# MCU.net
KiCad netlist of a schematic drawn in Altium Designer
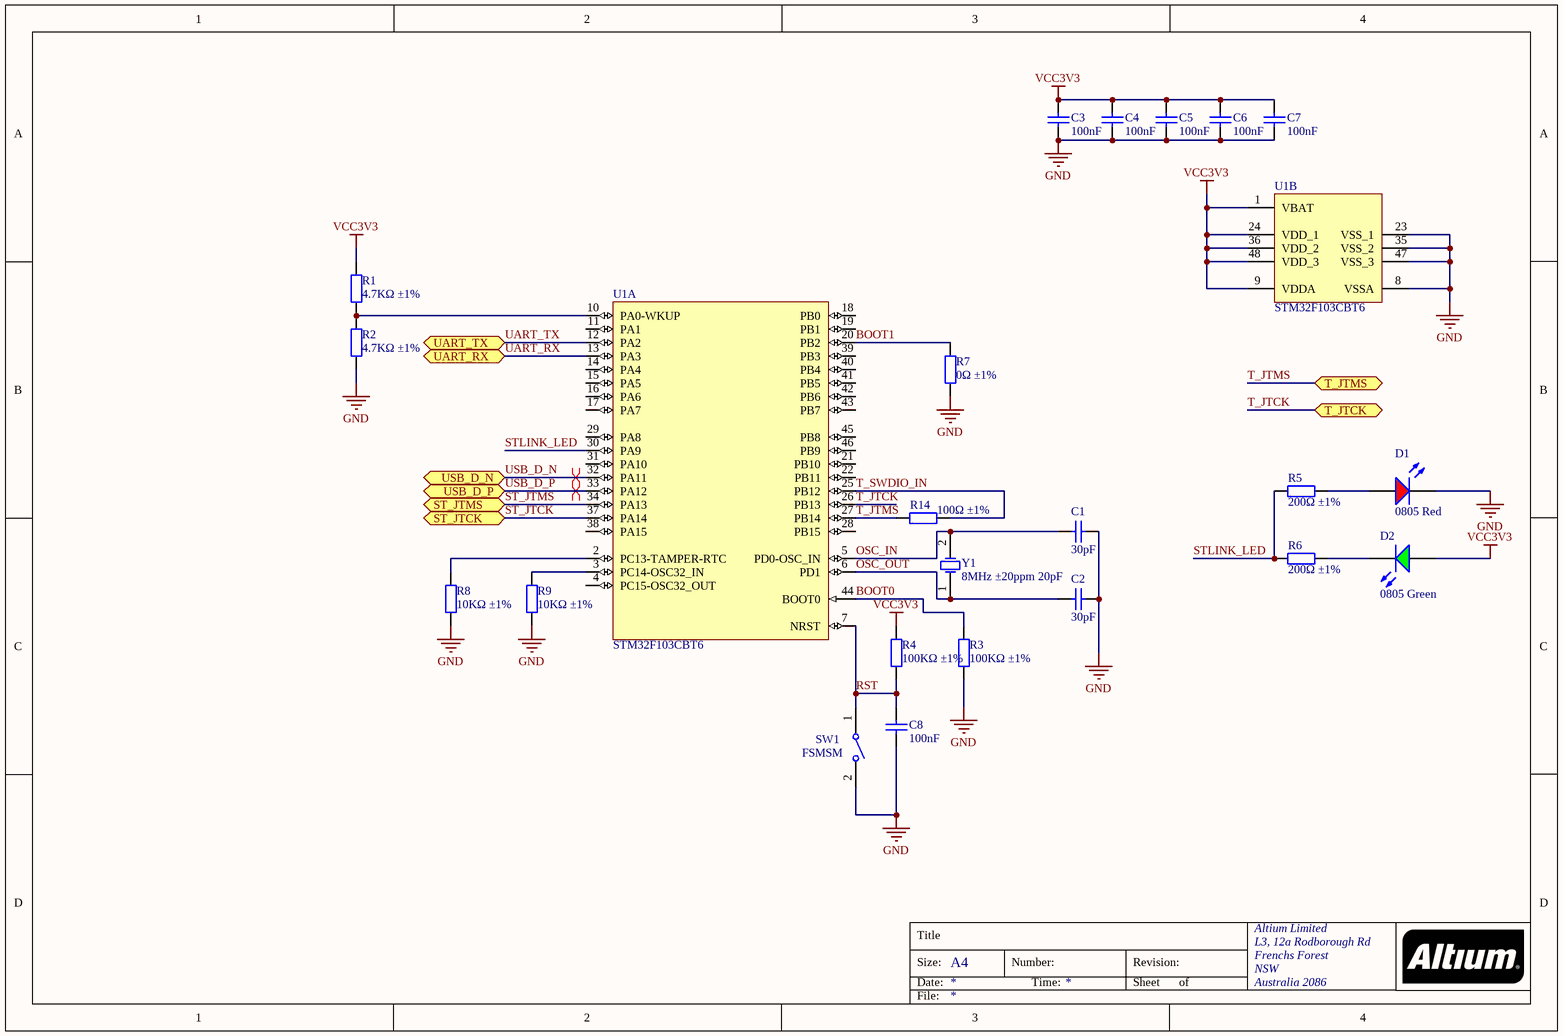
[diagram p0: MCU.SchDoc]

(export (version "E")
  (design (tool "Eeschema 10.0.6"))
  (components
    (comp (ref "C1")
      (value "30pF")
      (footprint "0402_C")
      (description "Chip capacitors")
      (fields
        (field (name "MANUFACTURER") "Guangdong Fenghua Advanced Tech")
        (field (name "PARTNUMBER") "0402CG300J500NT")
      )
      (libsource (lib "Miscellaneous Devices LC") (part "0402 30pF (300) 5% 50V"))
    )
    (comp (ref "C2")
      (value "30pF")
      (footprint "0402_C")
      (description "Chip capacitors")
      (fields
        (field (name "MANUFACTURER") "Guangdong Fenghua Advanced Tech")
        (field (name "PARTNUMBER") "0402CG300J500NT")
      )
      (libsource (lib "Miscellaneous Devices LC") (part "0402 30pF (300) 5% 50V"))
    )
    (comp (ref "C3")
      (value "100nF")
      (footprint "0402_C")
      (description "Chip capacitors")
      (fields
        (field (name "MANUFACTURER") "Samsung Electro-Mechanics")
        (field (name "PARTNUMBER") "CL05B104KO5NNNC")
      )
      (libsource (lib "Miscellaneous Devices LC") (part "0402 100nF (104) 10% 16V"))
    )
    (comp (ref "C4")
      (value "100nF")
      (footprint "0402_C")
      (description "Chip capacitors")
      (fields
        (field (name "MANUFACTURER") "Samsung Electro-Mechanics")
        (field (name "PARTNUMBER") "CL05B104KO5NNNC")
      )
      (libsource (lib "Miscellaneous Devices LC") (part "0402 100nF (104) 10% 16V"))
    )
    (comp (ref "C5")
      (value "100nF")
      (footprint "0402_C")
      (description "Chip capacitors")
      (fields
        (field (name "MANUFACTURER") "Samsung Electro-Mechanics")
        (field (name "PARTNUMBER") "CL05B104KO5NNNC")
      )
      (libsource (lib "Miscellaneous Devices LC") (part "0402 100nF (104) 10% 16V"))
    )
    (comp (ref "C6")
      (value "100nF")
      (footprint "0402_C")
      (description "Chip capacitors")
      (fields
        (field (name "MANUFACTURER") "Samsung Electro-Mechanics")
        (field (name "PARTNUMBER") "CL05B104KO5NNNC")
      )
      (libsource (lib "Miscellaneous Devices LC") (part "0402 100nF (104) 10% 16V"))
    )
    (comp (ref "C7")
      (value "100nF")
      (footprint "0402_C")
      (description "Chip capacitors")
      (fields
        (field (name "MANUFACTURER") "Samsung Electro-Mechanics")
        (field (name "PARTNUMBER") "CL05B104KO5NNNC")
      )
      (libsource (lib "Miscellaneous Devices LC") (part "0402 100nF (104) 10% 16V"))
    )
    (comp (ref "C8")
      (value "100nF")
      (footprint "0402_C")
      (description "Chip capacitors")
      (fields
        (field (name "MANUFACTURER") "Samsung Electro-Mechanics")
        (field (name "PARTNUMBER") "CL05B104KO5NNNC")
      )
      (libsource (lib "Miscellaneous Devices LC") (part "0402 100nF (104) 10% 16V"))
    )
    (comp (ref "D1")
      (value "0805 Red")
      (footprint "0805_LED_S1")
      (description "LED")
      (libsource (lib "Miscellaneous Devices LC") (part "0805 LED Red"))
    )
    (comp (ref "D2")
      (value "0805 Green")
      (footprint "0805_LED_S1")
      (description "LED")
      (libsource (lib "Miscellaneous Devices LC") (part "0805 LED Green"))
    )
    (comp (ref "R1")
      (value "4.7KΩ ±1%")
      (footprint "0805_R")
      (description "Chip resistor")
      (fields (field (name "MANUFACTURER") "Uniroyal Elec") (field (name "POWER") "1/8W"))
      (libsource (lib "Miscellaneous Devices LC") (part "0805 4.7K (4701) 1%"))
    )
    (comp (ref "R2")
      (value "4.7KΩ ±1%")
      (footprint "0805_R")
      (description "Chip resistor")
      (fields (field (name "MANUFACTURER") "Uniroyal Elec") (field (name "POWER") "1/8W"))
      (libsource (lib "Miscellaneous Devices LC") (part "0805 4.7K (4701) 1%"))
    )
    (comp (ref "R3")
      (value "100KΩ ±1%")
      (footprint "0402_R")
      (description "Chip resistor")
      (fields (field (name "MANUFACTURER") "Uniroyal Elec") (field (name "PARTNUMBER") "0402WGF1003TCE"))
      (libsource (lib "Miscellaneous Devices LC") (part "0402 100K (1003) 1%"))
    )
    (comp (ref "R4")
      (value "100KΩ ±1%")
      (footprint "0402_R")
      (description "Chip resistor")
      (fields (field (name "MANUFACTURER") "Uniroyal Elec") (field (name "PARTNUMBER") "0402WGF1003TCE"))
      (libsource (lib "Miscellaneous Devices LC") (part "0402 100K (1003) 1%"))
    )
    (comp (ref "R5")
      (value "200Ω ±1%")
      (footprint "0402_R")
      (description "Chip resistor")
      (fields (field (name "MANUFACTURER") "Uniroyal Elec") (field (name "PARTNUMBER") "0402WGF2000TCE"))
      (libsource (lib "Miscellaneous Devices LC") (part "0402 200R (2000) 1%"))
    )
    (comp (ref "R6")
      (value "200Ω ±1%")
      (footprint "0402_R")
      (description "Chip resistor")
      (fields (field (name "MANUFACTURER") "Uniroyal Elec") (field (name "PARTNUMBER") "0402WGF2000TCE"))
      (libsource (lib "Miscellaneous Devices LC") (part "0402 200R (2000) 1%"))
    )
    (comp (ref "R7")
      (value "0Ω ±1%")
      (footprint "0402_R")
      (description "Chip resistor")
      (fields (field (name "POWER") "1/16W") (field (name "MANUFACTURER") "Uniroyal Elec"))
      (libsource (lib "Miscellaneous Devices LC") (part "0402 0R (0R0) 1%"))
    )
    (comp (ref "R8")
      (value "10KΩ ±1%")
      (footprint "0402_R")
      (description "Chip resistor")
      (fields (field (name "MANUFACTURER") "Uniroyal Elec") (field (name "PARTNUMBER") "0402WGF1002TCE"))
      (libsource (lib "Miscellaneous Devices LC") (part "0402 10K (1002) 1%"))
    )
    (comp (ref "R9")
      (value "10KΩ ±1%")
      (footprint "0402_R")
      (description "Chip resistor")
      (fields (field (name "MANUFACTURER") "Uniroyal Elec") (field (name "PARTNUMBER") "0402WGF1002TCE"))
      (libsource (lib "Miscellaneous Devices LC") (part "0402 10K (1002) 1%"))
    )
    (comp (ref "R14")
      (value "100Ω ±1%")
      (footprint "0402_R")
      (description "Chip resistor")
      (fields (field (name "MANUFACTURER") "Uniroyal Elec") (field (name "PARTNUMBER") "0402WGF1000TCE"))
      (libsource (lib "Miscellaneous Devices LC") (part "0402 100R (1000) 1%"))
    )
    (comp (ref "SW1")
      (value "FSMSM")
      (footprint "TECO-FSMSM-2_V")
      (description "FSMSM Push Button Switch, 50 mA, -35 to 85 degC, 2-Pin SMD, RoHS, Bulk")
      (fields (field (name "MANUFACTURER") "TE Connectivity"))
      (libsource (lib "Altium Content Vault") (part "SW-SPST-2_C"))
    )
    (comp (ref "U1")
      (value "STM32F103CBT6")
      (footprint "LQFP-48_7x7x05P")
      (description "ARM")
      (libsource (lib "Miscellaneous Devices LC") (part "STM32F103CBT6"))
    )
    (comp (ref "Y1")
      (value "8MHz ±20ppm 20pF")
      (footprint "SMD-5032_2P")
      (description "贴片晶振")
      (libsource (lib "Miscellaneous Devices LC") (part "SMD-5032_2P 8MHz 20ppm 20pF"))
    )
  )
  (nets
    (net (code "1") (name "/BOOT0") (class "Default")
      (node (ref "R3") (pin "2") (pinfunction "2_2") (pintype "passive"))
      (node (ref "U1") (pin "44") (pinfunction "BOOT0_44") (pintype "input"))
    )
    (net (code "2") (name "/BOOT1") (class "Default")
      (node (ref "R7") (pin "2") (pinfunction "2_2") (pintype "passive"))
      (node (ref "U1") (pin "20") (pinfunction "PB2_20") (pintype "bidirectional"))
    )
    (net (code "3") (name "/OSC_IN") (class "Default")
      (node (ref "C1") (pin "1") (pinfunction "1_1") (pintype "passive"))
      (node (ref "U1") (pin "5") (pinfunction "PD0-OSC_IN_5") (pintype "bidirectional"))
      (node (ref "Y1") (pin "2") (pinfunction "OSC2_2") (pintype "passive"))
    )
    (net (code "4") (name "/OSC_OUT") (class "Default")
      (node (ref "C2") (pin "1") (pinfunction "1_1") (pintype "passive"))
      (node (ref "U1") (pin "6") (pinfunction "PD1_6") (pintype "bidirectional"))
      (node (ref "Y1") (pin "1") (pinfunction "OSC1_1") (pintype "passive"))
    )
    (net (code "5") (name "/RST") (class "Default")
      (node (ref "C8") (pin "2") (pinfunction "2_2") (pintype "passive"))
      (node (ref "R4") (pin "1") (pinfunction "1_1") (pintype "passive"))
      (node (ref "SW1") (pin "1") (pinfunction "1_1") (pintype "passive"))
      (node (ref "U1") (pin "7") (pinfunction "NRST_7") (pintype "bidirectional"))
    )
    (net (code "6") (name "/STLINK_LED") (class "Default")
      (node (ref "R5") (pin "1") (pinfunction "1_1") (pintype "passive"))
      (node (ref "R6") (pin "1") (pinfunction "1_1") (pintype "passive"))
      (node (ref "U1") (pin "30") (pinfunction "PA9_30") (pintype "bidirectional"))
    )
    (net (code "7") (name "/ST_JTCK") (class "Default")
      (node (ref "U1") (pin "37") (pinfunction "PA14_37") (pintype "bidirectional"))
    )
    (net (code "8") (name "/ST_JTMS") (class "Default")
      (node (ref "U1") (pin "34") (pinfunction "PA13_34") (pintype "bidirectional"))
    )
    (net (code "9") (name "/T_JTCK") (class "Default")
      (node (ref "U1") (pin "26") (pinfunction "PB13_26") (pintype "bidirectional"))
    )
    (net (code "10") (name "/T_JTMS") (class "Default")
      (node (ref "R14") (pin "2") (pinfunction "2_2") (pintype "passive"))
      (node (ref "U1") (pin "27") (pinfunction "PB14_27") (pintype "bidirectional"))
    )
    (net (code "11") (name "/T_SWDIO_IN") (class "Default")
      (node (ref "R14") (pin "1") (pinfunction "1_1") (pintype "passive"))
      (node (ref "U1") (pin "25") (pinfunction "PB12_25") (pintype "bidirectional"))
    )
    (net (code "12") (name "/UART_RX") (class "Default")
      (node (ref "U1") (pin "13") (pinfunction "PA3_13") (pintype "bidirectional"))
    )
    (net (code "13") (name "/UART_TX") (class "Default")
      (node (ref "U1") (pin "12") (pinfunction "PA2_12") (pintype "bidirectional"))
    )
    (net (code "14") (name "/USB_D_N") (class "Default")
      (node (ref "U1") (pin "32") (pinfunction "PA11_32") (pintype "bidirectional"))
    )
    (net (code "15") (name "/USB_D_P") (class "Default")
      (node (ref "U1") (pin "33") (pinfunction "PA12_33") (pintype "bidirectional"))
    )
    (net (code "16") (name "GND") (class "Default")
      (node (ref "C1") (pin "2") (pinfunction "2_2") (pintype "passive"))
      (node (ref "C2") (pin "2") (pinfunction "2_2") (pintype "passive"))
      (node (ref "C3") (pin "1") (pinfunction "1_1") (pintype "passive"))
      (node (ref "C4") (pin "1") (pinfunction "1_1") (pintype "passive"))
      (node (ref "C5") (pin "1") (pinfunction "1_1") (pintype "passive"))
      (node (ref "C6") (pin "1") (pinfunction "1_1") (pintype "passive"))
      (node (ref "C7") (pin "1") (pinfunction "1_1") (pintype "passive"))
      (node (ref "C8") (pin "1") (pinfunction "1_1") (pintype "passive"))
      (node (ref "D1") (pin "K") (pinfunction "K_K") (pintype "passive"))
      (node (ref "R2") (pin "1") (pinfunction "1_1") (pintype "passive"))
      (node (ref "R3") (pin "1") (pinfunction "1_1") (pintype "passive"))
      (node (ref "R7") (pin "1") (pinfunction "1_1") (pintype "passive"))
      (node (ref "R8") (pin "1") (pinfunction "1_1") (pintype "passive"))
      (node (ref "R9") (pin "1") (pinfunction "1_1") (pintype "passive"))
      (node (ref "SW1") (pin "2") (pinfunction "2_2") (pintype "passive"))
      (node (ref "U1") (pin "23") (pinfunction "VSS_1_23") (pintype "power_in"))
      (node (ref "U1") (pin "35") (pinfunction "VSS_2_35") (pintype "power_in"))
      (node (ref "U1") (pin "47") (pinfunction "VSS_3_47") (pintype "power_in"))
      (node (ref "U1") (pin "8") (pinfunction "VSSA_8") (pintype "power_in"))
    )
    (net (code "17") (name "Net-(D1-PadA)") (class "Default")
      (node (ref "D1") (pin "A") (pinfunction "A_A") (pintype "passive"))
      (node (ref "R5") (pin "2") (pinfunction "2_2") (pintype "passive"))
    )
    (net (code "18") (name "Net-(D2-PadK)") (class "Default")
      (node (ref "D2") (pin "K") (pinfunction "K_K") (pintype "passive"))
      (node (ref "R6") (pin "2") (pinfunction "2_2") (pintype "passive"))
    )
    (net (code "19") (name "Net-(U1A-PA0-WKUP)") (class "Default")
      (node (ref "R1") (pin "1") (pinfunction "1_1") (pintype "passive"))
      (node (ref "R2") (pin "2") (pinfunction "2_2") (pintype "passive"))
      (node (ref "U1") (pin "10") (pinfunction "PA0-WKUP_10") (pintype "bidirectional"))
    )
    (net (code "20") (name "Net-(U1A-PC13-TAMPER-RTC)") (class "Default")
      (node (ref "R8") (pin "2") (pinfunction "2_2") (pintype "passive"))
      (node (ref "U1") (pin "2") (pinfunction "PC13-TAMPER-RTC_2") (pintype "bidirectional"))
    )
    (net (code "21") (name "Net-(U1A-PC14-OSC32_IN)") (class "Default")
      (node (ref "R9") (pin "2") (pinfunction "2_2") (pintype "passive"))
      (node (ref "U1") (pin "3") (pinfunction "PC14-OSC32_IN_3") (pintype "bidirectional"))
    )
    (net (code "22") (name "VCC3V3") (class "Default")
      (node (ref "C3") (pin "2") (pinfunction "2_2") (pintype "passive"))
      (node (ref "C4") (pin "2") (pinfunction "2_2") (pintype "passive"))
      (node (ref "C5") (pin "2") (pinfunction "2_2") (pintype "passive"))
      (node (ref "C6") (pin "2") (pinfunction "2_2") (pintype "passive"))
      (node (ref "C7") (pin "2") (pinfunction "2_2") (pintype "passive"))
      (node (ref "D2") (pin "A") (pinfunction "A_A") (pintype "passive"))
      (node (ref "R1") (pin "2") (pinfunction "2_2") (pintype "passive"))
      (node (ref "R4") (pin "2") (pinfunction "2_2") (pintype "passive"))
      (node (ref "U1") (pin "1") (pinfunction "VBAT_1") (pintype "power_in"))
      (node (ref "U1") (pin "24") (pinfunction "VDD_1_24") (pintype "power_in"))
      (node (ref "U1") (pin "36") (pinfunction "VDD_2_36") (pintype "power_in"))
      (node (ref "U1") (pin "48") (pinfunction "VDD_3_48") (pintype "power_in"))
      (node (ref "U1") (pin "9") (pinfunction "VDDA_9") (pintype "power_in"))
    )
    (net (code "23") (name "unconnected-(U1A-PA1-Pad11)") (class "Default")
      (node (ref "U1") (pin "11") (pinfunction "PA1_11") (pintype "bidirectional"))
    )
    (net (code "24") (name "unconnected-(U1A-PA4-Pad14)") (class "Default")
      (node (ref "U1") (pin "14") (pinfunction "PA4_14") (pintype "bidirectional"))
    )
    (net (code "25") (name "unconnected-(U1A-PA5-Pad15)") (class "Default")
      (node (ref "U1") (pin "15") (pinfunction "PA5_15") (pintype "bidirectional"))
    )
    (net (code "26") (name "unconnected-(U1A-PA6-Pad16)") (class "Default")
      (node (ref "U1") (pin "16") (pinfunction "PA6_16") (pintype "bidirectional"))
    )
    (net (code "27") (name "unconnected-(U1A-PA7-Pad17)") (class "Default")
      (node (ref "U1") (pin "17") (pinfunction "PA7_17") (pintype "bidirectional"))
    )
    (net (code "28") (name "unconnected-(U1A-PA8-Pad29)") (class "Default")
      (node (ref "U1") (pin "29") (pinfunction "PA8_29") (pintype "bidirectional"))
    )
    (net (code "29") (name "unconnected-(U1A-PA10-Pad31)") (class "Default")
      (node (ref "U1") (pin "31") (pinfunction "PA10_31") (pintype "bidirectional"))
    )
    (net (code "30") (name "unconnected-(U1A-PA15-Pad38)") (class "Default")
      (node (ref "U1") (pin "38") (pinfunction "PA15_38") (pintype "bidirectional"))
    )
    (net (code "31") (name "unconnected-(U1A-PB0-Pad18)") (class "Default")
      (node (ref "U1") (pin "18") (pinfunction "PB0_18") (pintype "bidirectional"))
    )
    (net (code "32") (name "unconnected-(U1A-PB1-Pad19)") (class "Default")
      (node (ref "U1") (pin "19") (pinfunction "PB1_19") (pintype "bidirectional"))
    )
    (net (code "33") (name "unconnected-(U1A-PB3-Pad39)") (class "Default")
      (node (ref "U1") (pin "39") (pinfunction "PB3_39") (pintype "bidirectional"))
    )
    (net (code "34") (name "unconnected-(U1A-PB4-Pad40)") (class "Default")
      (node (ref "U1") (pin "40") (pinfunction "PB4_40") (pintype "bidirectional"))
    )
    (net (code "35") (name "unconnected-(U1A-PB5-Pad41)") (class "Default")
      (node (ref "U1") (pin "41") (pinfunction "PB5_41") (pintype "bidirectional"))
    )
    (net (code "36") (name "unconnected-(U1A-PB6-Pad42)") (class "Default")
      (node (ref "U1") (pin "42") (pinfunction "PB6_42") (pintype "bidirectional"))
    )
    (net (code "37") (name "unconnected-(U1A-PB7-Pad43)") (class "Default")
      (node (ref "U1") (pin "43") (pinfunction "PB7_43") (pintype "bidirectional"))
    )
    (net (code "38") (name "unconnected-(U1A-PB8-Pad45)") (class "Default")
      (node (ref "U1") (pin "45") (pinfunction "PB8_45") (pintype "bidirectional"))
    )
    (net (code "39") (name "unconnected-(U1A-PB9-Pad46)") (class "Default")
      (node (ref "U1") (pin "46") (pinfunction "PB9_46") (pintype "bidirectional"))
    )
    (net (code "40") (name "unconnected-(U1A-PB10-Pad21)") (class "Default")
      (node (ref "U1") (pin "21") (pinfunction "PB10_21") (pintype "bidirectional"))
    )
    (net (code "41") (name "unconnected-(U1A-PB11-Pad22)") (class "Default")
      (node (ref "U1") (pin "22") (pinfunction "PB11_22") (pintype "bidirectional"))
    )
    (net (code "42") (name "unconnected-(U1A-PB15-Pad28)") (class "Default")
      (node (ref "U1") (pin "28") (pinfunction "PB15_28") (pintype "bidirectional"))
    )
    (net (code "43") (name "unconnected-(U1A-PC15-OSC32_OUT-Pad4)") (class "Default")
      (node (ref "U1") (pin "4") (pinfunction "PC15-OSC32_OUT_4") (pintype "bidirectional"))
    )
  )
)
